# M203B.net
KiCad netlist of a schematic drawn in EAGLE
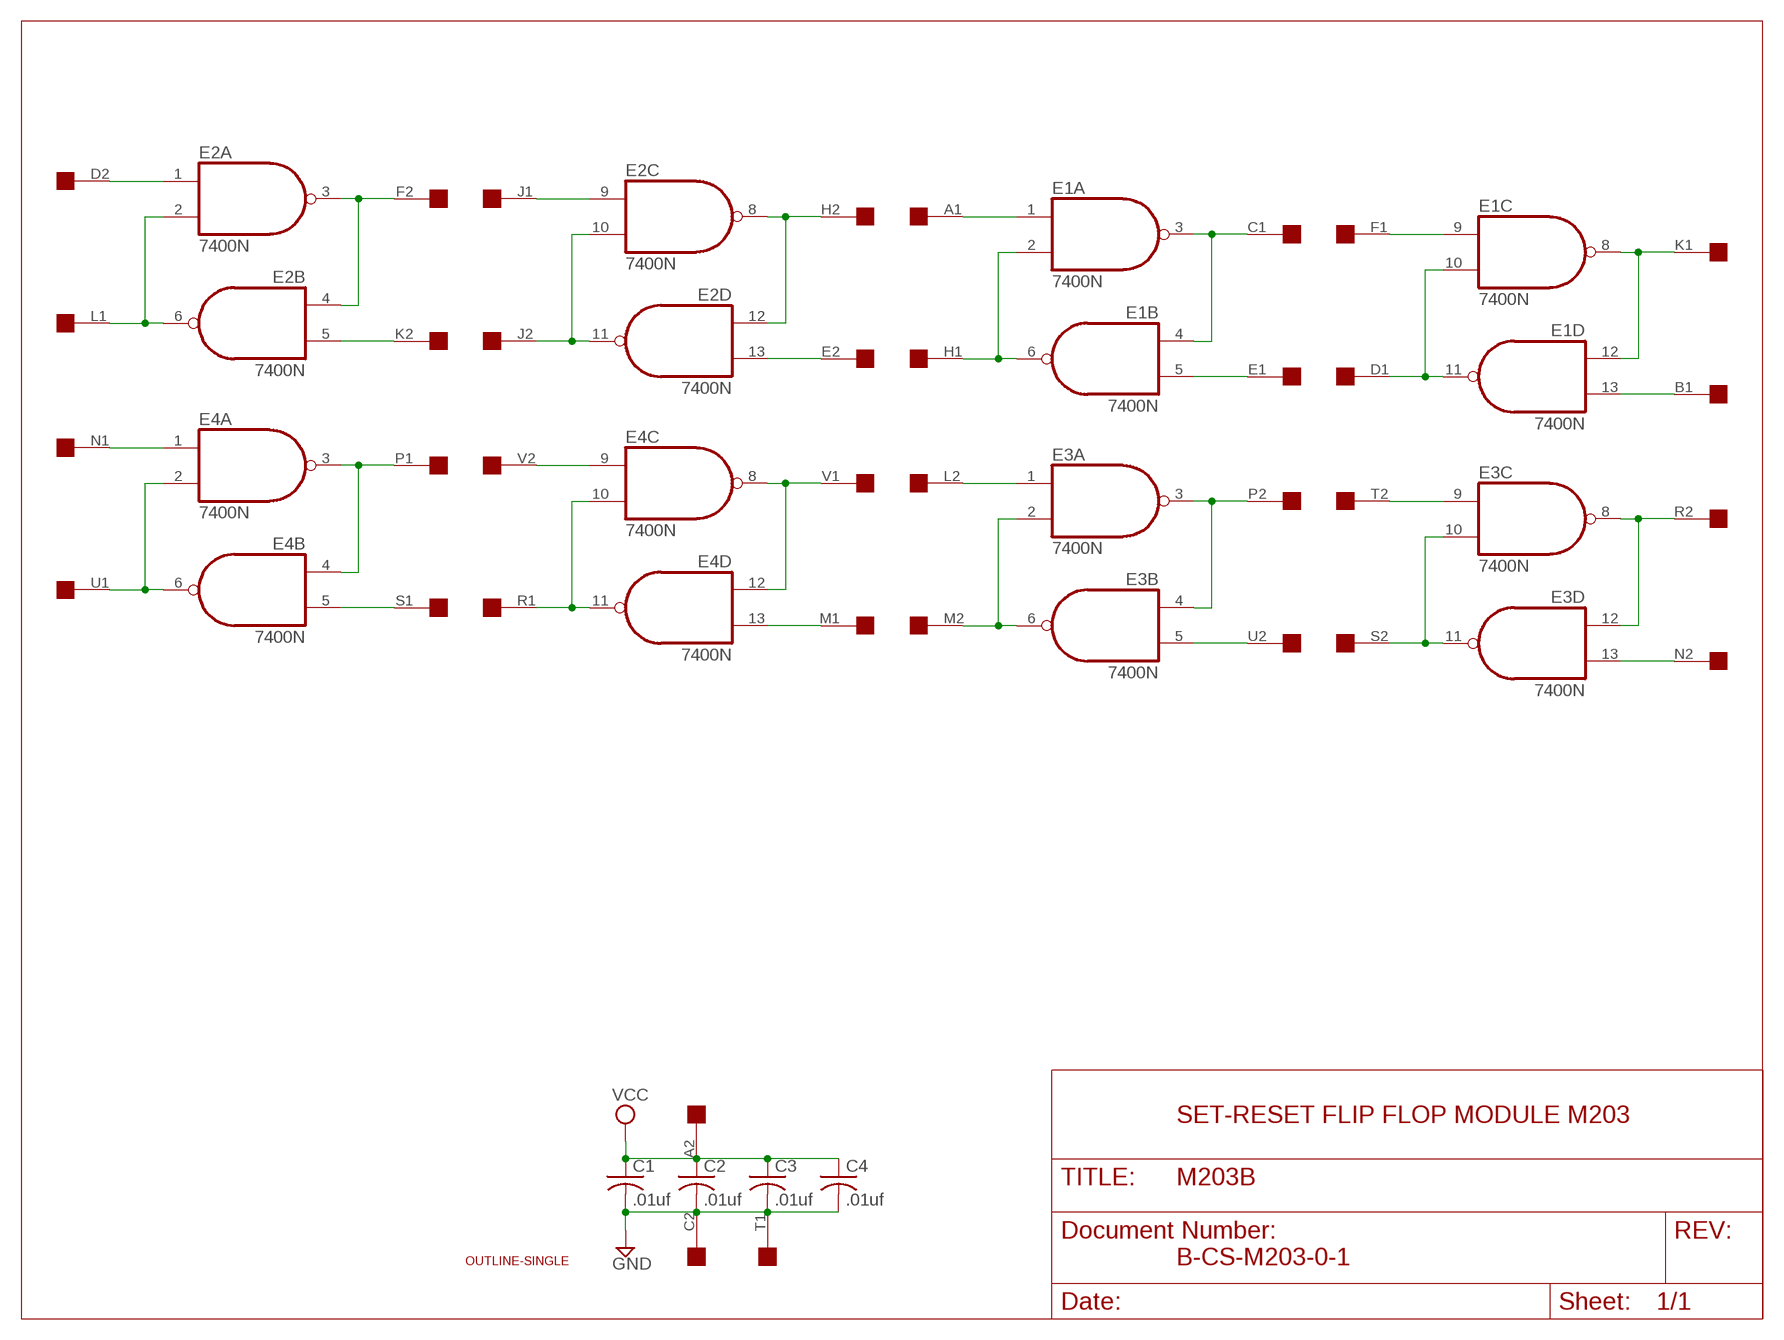
[diagram p0: schematic, sheet 1]

(export (version "E")
  (design (tool "Eeschema 10.0.6"))
  (components
    (comp (ref "C1")
      (value ".01uf")
      (footprint "eagle-import:C050-025X075")
      (libsource (lib "eagle-import") (part "C-US050-025X075"))
    )
    (comp (ref "C2")
      (value ".01uf")
      (footprint "eagle-import:C050-025X075")
      (libsource (lib "eagle-import") (part "C-US050-025X075"))
    )
    (comp (ref "C3")
      (value ".01uf")
      (footprint "eagle-import:C050-025X075")
      (libsource (lib "eagle-import") (part "C-US050-025X075"))
    )
    (comp (ref "C4")
      (value ".01uf")
      (footprint "eagle-import:C050-025X075")
      (libsource (lib "eagle-import") (part "C-US050-025X075"))
    )
    (comp (ref "E1")
      (value "7400N")
      (footprint "eagle-import:DIL14")
      (libsource (lib "eagle-import") (part "7400N"))
    )
    (comp (ref "E2")
      (value "7400N")
      (footprint "eagle-import:DIL14")
      (libsource (lib "eagle-import") (part "7400N"))
    )
    (comp (ref "E3")
      (value "7400N")
      (footprint "eagle-import:DIL14")
      (libsource (lib "eagle-import") (part "7400N"))
    )
    (comp (ref "E4")
      (value "7400N")
      (footprint "eagle-import:DIL14")
      (libsource (lib "eagle-import") (part "7400N"))
    )
    (comp (ref "U$1")
      (value "OUTLINE-SINGLE")
      (footprint "eagle-import:SINGLE")
      (libsource (lib "eagle-import") (part "OUTLINE-SINGLE"))
    )
    (comp (ref "U$2")
      (value "EDGE-2CONNECTOR")
      (footprint "eagle-import:EDGE-CON2")
      (libsource (lib "eagle-import") (part "EDGE-2CONNECTOR"))
    )
  )
  (nets
    (net (code "1") (name "GND") (class "Default")
      (node (ref "C1") (pin "2") (pinfunction "2_2") (pintype "passive"))
      (node (ref "C2") (pin "2") (pinfunction "2_2") (pintype "passive"))
      (node (ref "C3") (pin "2") (pinfunction "2_2") (pintype "passive"))
      (node (ref "C4") (pin "2") (pinfunction "2_2") (pintype "passive"))
      (node (ref "U$2") (pin "C2") (pinfunction "1_C2") (pintype "bidirectional"))
      (node (ref "U$2") (pin "T1") (pinfunction "1_T1") (pintype "bidirectional"))
    )
    (net (code "2") (name "Net-(E1A-I0)") (class "Default")
      (node (ref "E1") (pin "1") (pinfunction "I0_1") (pintype "input"))
      (node (ref "U$2") (pin "A1") (pinfunction "1_A1") (pintype "bidirectional"))
    )
    (net (code "3") (name "Net-(E1A-I1)") (class "Default")
      (node (ref "E1") (pin "2") (pinfunction "I1_2") (pintype "input"))
      (node (ref "E1") (pin "6") (pinfunction "O_6") (pintype "output"))
      (node (ref "U$2") (pin "H1") (pinfunction "1_H1") (pintype "bidirectional"))
    )
    (net (code "4") (name "Net-(E1A-O)") (class "Default")
      (node (ref "E1") (pin "3") (pinfunction "O_3") (pintype "output"))
      (node (ref "E1") (pin "4") (pinfunction "I0_4") (pintype "input"))
      (node (ref "U$2") (pin "C1") (pinfunction "1_C1") (pintype "bidirectional"))
    )
    (net (code "5") (name "Net-(E1B-I1)") (class "Default")
      (node (ref "E1") (pin "5") (pinfunction "I1_5") (pintype "input"))
      (node (ref "U$2") (pin "E1") (pinfunction "1_E1") (pintype "bidirectional"))
    )
    (net (code "6") (name "Net-(E1C-I0)") (class "Default")
      (node (ref "E1") (pin "9") (pinfunction "I0_9") (pintype "input"))
      (node (ref "U$2") (pin "F1") (pinfunction "1_F1") (pintype "bidirectional"))
    )
    (net (code "7") (name "Net-(E1C-I1)") (class "Default")
      (node (ref "E1") (pin "10") (pinfunction "I1_10") (pintype "input"))
      (node (ref "E1") (pin "11") (pinfunction "O_11") (pintype "output"))
      (node (ref "U$2") (pin "D1") (pinfunction "1_D1") (pintype "bidirectional"))
    )
    (net (code "8") (name "Net-(E1C-O)") (class "Default")
      (node (ref "E1") (pin "12") (pinfunction "I0_12") (pintype "input"))
      (node (ref "E1") (pin "8") (pinfunction "O_8") (pintype "output"))
      (node (ref "U$2") (pin "K1") (pinfunction "1_K1") (pintype "bidirectional"))
    )
    (net (code "9") (name "Net-(E1D-I1)") (class "Default")
      (node (ref "E1") (pin "13") (pinfunction "I1_13") (pintype "input"))
      (node (ref "U$2") (pin "B1") (pinfunction "1_B1") (pintype "bidirectional"))
    )
    (net (code "10") (name "Net-(E2A-I0)") (class "Default")
      (node (ref "E2") (pin "1") (pinfunction "I0_1") (pintype "input"))
      (node (ref "U$2") (pin "D2") (pinfunction "1_D2") (pintype "bidirectional"))
    )
    (net (code "11") (name "Net-(E2A-I1)") (class "Default")
      (node (ref "E2") (pin "2") (pinfunction "I1_2") (pintype "input"))
      (node (ref "E2") (pin "6") (pinfunction "O_6") (pintype "output"))
      (node (ref "U$2") (pin "L1") (pinfunction "1_L1") (pintype "bidirectional"))
    )
    (net (code "12") (name "Net-(E2A-O)") (class "Default")
      (node (ref "E2") (pin "3") (pinfunction "O_3") (pintype "output"))
      (node (ref "E2") (pin "4") (pinfunction "I0_4") (pintype "input"))
      (node (ref "U$2") (pin "F2") (pinfunction "1_F2") (pintype "bidirectional"))
    )
    (net (code "13") (name "Net-(E2B-I1)") (class "Default")
      (node (ref "E2") (pin "5") (pinfunction "I1_5") (pintype "input"))
      (node (ref "U$2") (pin "K2") (pinfunction "1_K2") (pintype "bidirectional"))
    )
    (net (code "14") (name "Net-(E2C-I0)") (class "Default")
      (node (ref "E2") (pin "9") (pinfunction "I0_9") (pintype "input"))
      (node (ref "U$2") (pin "J1") (pinfunction "1_J1") (pintype "bidirectional"))
    )
    (net (code "15") (name "Net-(E2C-I1)") (class "Default")
      (node (ref "E2") (pin "10") (pinfunction "I1_10") (pintype "input"))
      (node (ref "E2") (pin "11") (pinfunction "O_11") (pintype "output"))
      (node (ref "U$2") (pin "J2") (pinfunction "1_J2") (pintype "bidirectional"))
    )
    (net (code "16") (name "Net-(E2C-O)") (class "Default")
      (node (ref "E2") (pin "12") (pinfunction "I0_12") (pintype "input"))
      (node (ref "E2") (pin "8") (pinfunction "O_8") (pintype "output"))
      (node (ref "U$2") (pin "H2") (pinfunction "1_H2") (pintype "bidirectional"))
    )
    (net (code "17") (name "Net-(E2D-I1)") (class "Default")
      (node (ref "E2") (pin "13") (pinfunction "I1_13") (pintype "input"))
      (node (ref "U$2") (pin "E2") (pinfunction "1_E2") (pintype "bidirectional"))
    )
    (net (code "18") (name "Net-(E3A-I0)") (class "Default")
      (node (ref "E3") (pin "1") (pinfunction "I0_1") (pintype "input"))
      (node (ref "U$2") (pin "L2") (pinfunction "1_L2") (pintype "bidirectional"))
    )
    (net (code "19") (name "Net-(E3A-I1)") (class "Default")
      (node (ref "E3") (pin "2") (pinfunction "I1_2") (pintype "input"))
      (node (ref "E3") (pin "6") (pinfunction "O_6") (pintype "output"))
      (node (ref "U$2") (pin "M2") (pinfunction "1_M2") (pintype "bidirectional"))
    )
    (net (code "20") (name "Net-(E3A-O)") (class "Default")
      (node (ref "E3") (pin "3") (pinfunction "O_3") (pintype "output"))
      (node (ref "E3") (pin "4") (pinfunction "I0_4") (pintype "input"))
      (node (ref "U$2") (pin "P2") (pinfunction "1_P2") (pintype "bidirectional"))
    )
    (net (code "21") (name "Net-(E3B-I1)") (class "Default")
      (node (ref "E3") (pin "5") (pinfunction "I1_5") (pintype "input"))
      (node (ref "U$2") (pin "U2") (pinfunction "1_U2") (pintype "bidirectional"))
    )
    (net (code "22") (name "Net-(E3C-I0)") (class "Default")
      (node (ref "E3") (pin "9") (pinfunction "I0_9") (pintype "input"))
      (node (ref "U$2") (pin "T2") (pinfunction "1_T2") (pintype "bidirectional"))
    )
    (net (code "23") (name "Net-(E3C-I1)") (class "Default")
      (node (ref "E3") (pin "10") (pinfunction "I1_10") (pintype "input"))
      (node (ref "E3") (pin "11") (pinfunction "O_11") (pintype "output"))
      (node (ref "U$2") (pin "S2") (pinfunction "1_S2") (pintype "bidirectional"))
    )
    (net (code "24") (name "Net-(E3C-O)") (class "Default")
      (node (ref "E3") (pin "12") (pinfunction "I0_12") (pintype "input"))
      (node (ref "E3") (pin "8") (pinfunction "O_8") (pintype "output"))
      (node (ref "U$2") (pin "R2") (pinfunction "1_R2") (pintype "bidirectional"))
    )
    (net (code "25") (name "Net-(E3D-I1)") (class "Default")
      (node (ref "E3") (pin "13") (pinfunction "I1_13") (pintype "input"))
      (node (ref "U$2") (pin "N2") (pinfunction "1_N2") (pintype "bidirectional"))
    )
    (net (code "26") (name "Net-(E4A-I0)") (class "Default")
      (node (ref "E4") (pin "1") (pinfunction "I0_1") (pintype "input"))
      (node (ref "U$2") (pin "N1") (pinfunction "1_N1") (pintype "bidirectional"))
    )
    (net (code "27") (name "Net-(E4A-I1)") (class "Default")
      (node (ref "E4") (pin "2") (pinfunction "I1_2") (pintype "input"))
      (node (ref "E4") (pin "6") (pinfunction "O_6") (pintype "output"))
      (node (ref "U$2") (pin "U1") (pinfunction "1_U1") (pintype "bidirectional"))
    )
    (net (code "28") (name "Net-(E4A-O)") (class "Default")
      (node (ref "E4") (pin "3") (pinfunction "O_3") (pintype "output"))
      (node (ref "E4") (pin "4") (pinfunction "I0_4") (pintype "input"))
      (node (ref "U$2") (pin "P1") (pinfunction "1_P1") (pintype "bidirectional"))
    )
    (net (code "29") (name "Net-(E4B-I1)") (class "Default")
      (node (ref "E4") (pin "5") (pinfunction "I1_5") (pintype "input"))
      (node (ref "U$2") (pin "S1") (pinfunction "1_S1") (pintype "bidirectional"))
    )
    (net (code "30") (name "Net-(E4C-I0)") (class "Default")
      (node (ref "E4") (pin "9") (pinfunction "I0_9") (pintype "input"))
      (node (ref "U$2") (pin "V2") (pinfunction "1_V2") (pintype "bidirectional"))
    )
    (net (code "31") (name "Net-(E4C-I1)") (class "Default")
      (node (ref "E4") (pin "10") (pinfunction "I1_10") (pintype "input"))
      (node (ref "E4") (pin "11") (pinfunction "O_11") (pintype "output"))
      (node (ref "U$2") (pin "R1") (pinfunction "1_R1") (pintype "bidirectional"))
    )
    (net (code "32") (name "Net-(E4C-O)") (class "Default")
      (node (ref "E4") (pin "12") (pinfunction "I0_12") (pintype "input"))
      (node (ref "E4") (pin "8") (pinfunction "O_8") (pintype "output"))
      (node (ref "U$2") (pin "V1") (pinfunction "1_V1") (pintype "bidirectional"))
    )
    (net (code "33") (name "Net-(E4D-I1)") (class "Default")
      (node (ref "E4") (pin "13") (pinfunction "I1_13") (pintype "input"))
      (node (ref "U$2") (pin "M1") (pinfunction "1_M1") (pintype "bidirectional"))
    )
    (net (code "34") (name "VCC") (class "Default")
      (node (ref "C1") (pin "1") (pinfunction "1_1") (pintype "passive"))
      (node (ref "C2") (pin "1") (pinfunction "1_1") (pintype "passive"))
      (node (ref "C3") (pin "1") (pinfunction "1_1") (pintype "passive"))
      (node (ref "C4") (pin "1") (pinfunction "1_1") (pintype "passive"))
      (node (ref "U$2") (pin "A2") (pinfunction "1_A2") (pintype "bidirectional"))
    )
  )
)
